# ProProject___2024-08-05.net
KiCad netlist of a schematic drawn in EasyEDA Pro
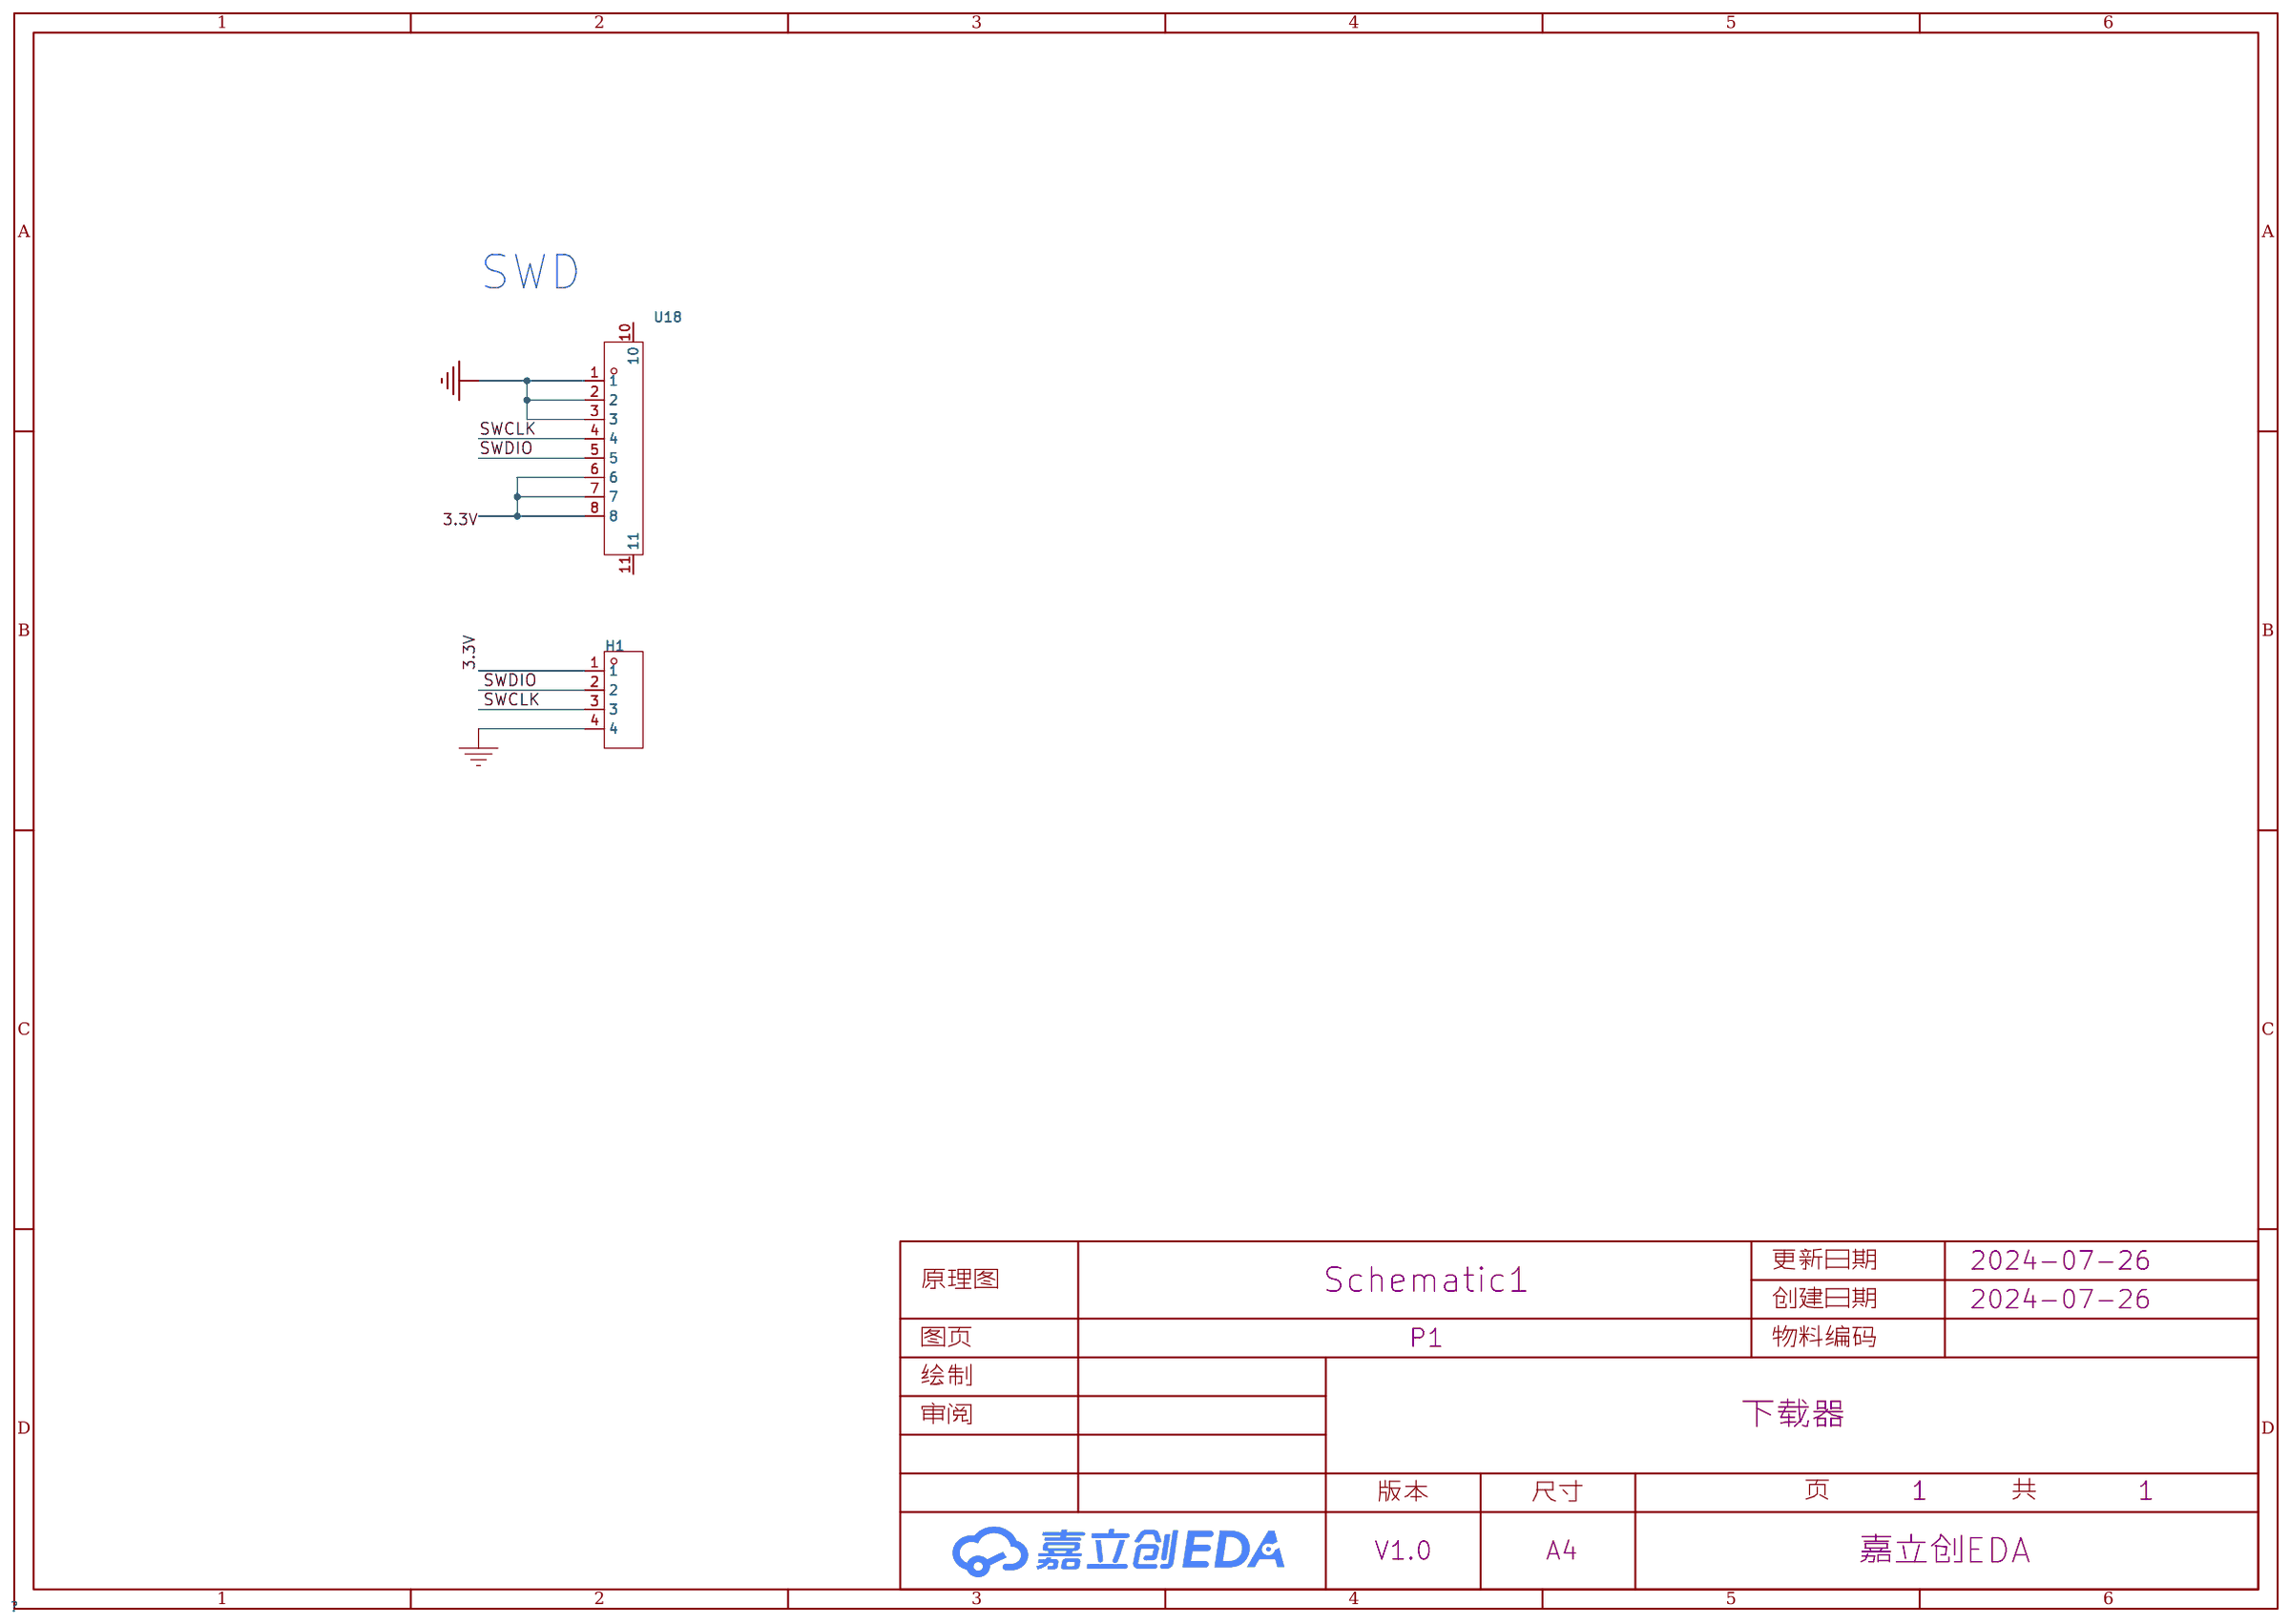
[diagram p0: schematic sheet]

(export (version "E")
  (design (tool "Eeschema 10.0.6"))
  (components
    (comp (ref "H1")
      (value "~")
      (footprint "easyedapro:HDR-TH_4P-P2.54-V-M")
      (libsource (lib "easyedapro") (part "PZ254V-11-04P"))
    )
    (comp (ref "U18")
      (value "SMTFPC连接器0.5MM间距翻盖8PIN")
      (footprint "easyedapro:FPC-SMD_AFC01-S08FCC-00")
      (libsource (lib "easyedapro") (part "SMTFPC连接器0.5MM间距翻盖8PIN"))
    )
  )
  (nets
    (net (code "1") (name "/3.3V") (class "Default")
      (node (ref "H1") (pin "1") (pinfunction "1_1") (pintype "unspecified"))
      (node (ref "U18") (pin "6") (pinfunction "6_6") (pintype "input"))
      (node (ref "U18") (pin "7") (pinfunction "7_7") (pintype "input"))
      (node (ref "U18") (pin "8") (pinfunction "8_8") (pintype "input"))
    )
    (net (code "2") (name "/SWCLK") (class "Default")
      (node (ref "H1") (pin "3") (pinfunction "3_3") (pintype "unspecified"))
      (node (ref "U18") (pin "4") (pinfunction "4_4") (pintype "input"))
    )
    (net (code "3") (name "/SWDIO") (class "Default")
      (node (ref "H1") (pin "2") (pinfunction "2_2") (pintype "unspecified"))
      (node (ref "U18") (pin "5") (pinfunction "5_5") (pintype "input"))
    )
    (net (code "4") (name "GND") (class "Default")
      (node (ref "H1") (pin "4") (pinfunction "4_4") (pintype "unspecified"))
      (node (ref "U18") (pin "1") (pinfunction "1_1") (pintype "input"))
      (node (ref "U18") (pin "2") (pinfunction "2_2") (pintype "input"))
      (node (ref "U18") (pin "3") (pinfunction "3_3") (pintype "input"))
    )
    (net (code "5") (name "unconnected-(U18-Pad10)") (class "Default")
      (node (ref "U18") (pin "10") (pinfunction "10_10") (pintype "input"))
    )
    (net (code "6") (name "unconnected-(U18-Pad11)") (class "Default")
      (node (ref "U18") (pin "11") (pinfunction "11_11") (pintype "input"))
    )
  )
)
